# arduino-configuration-shield.net
KiCad netlist of a schematic drawn in EAGLE
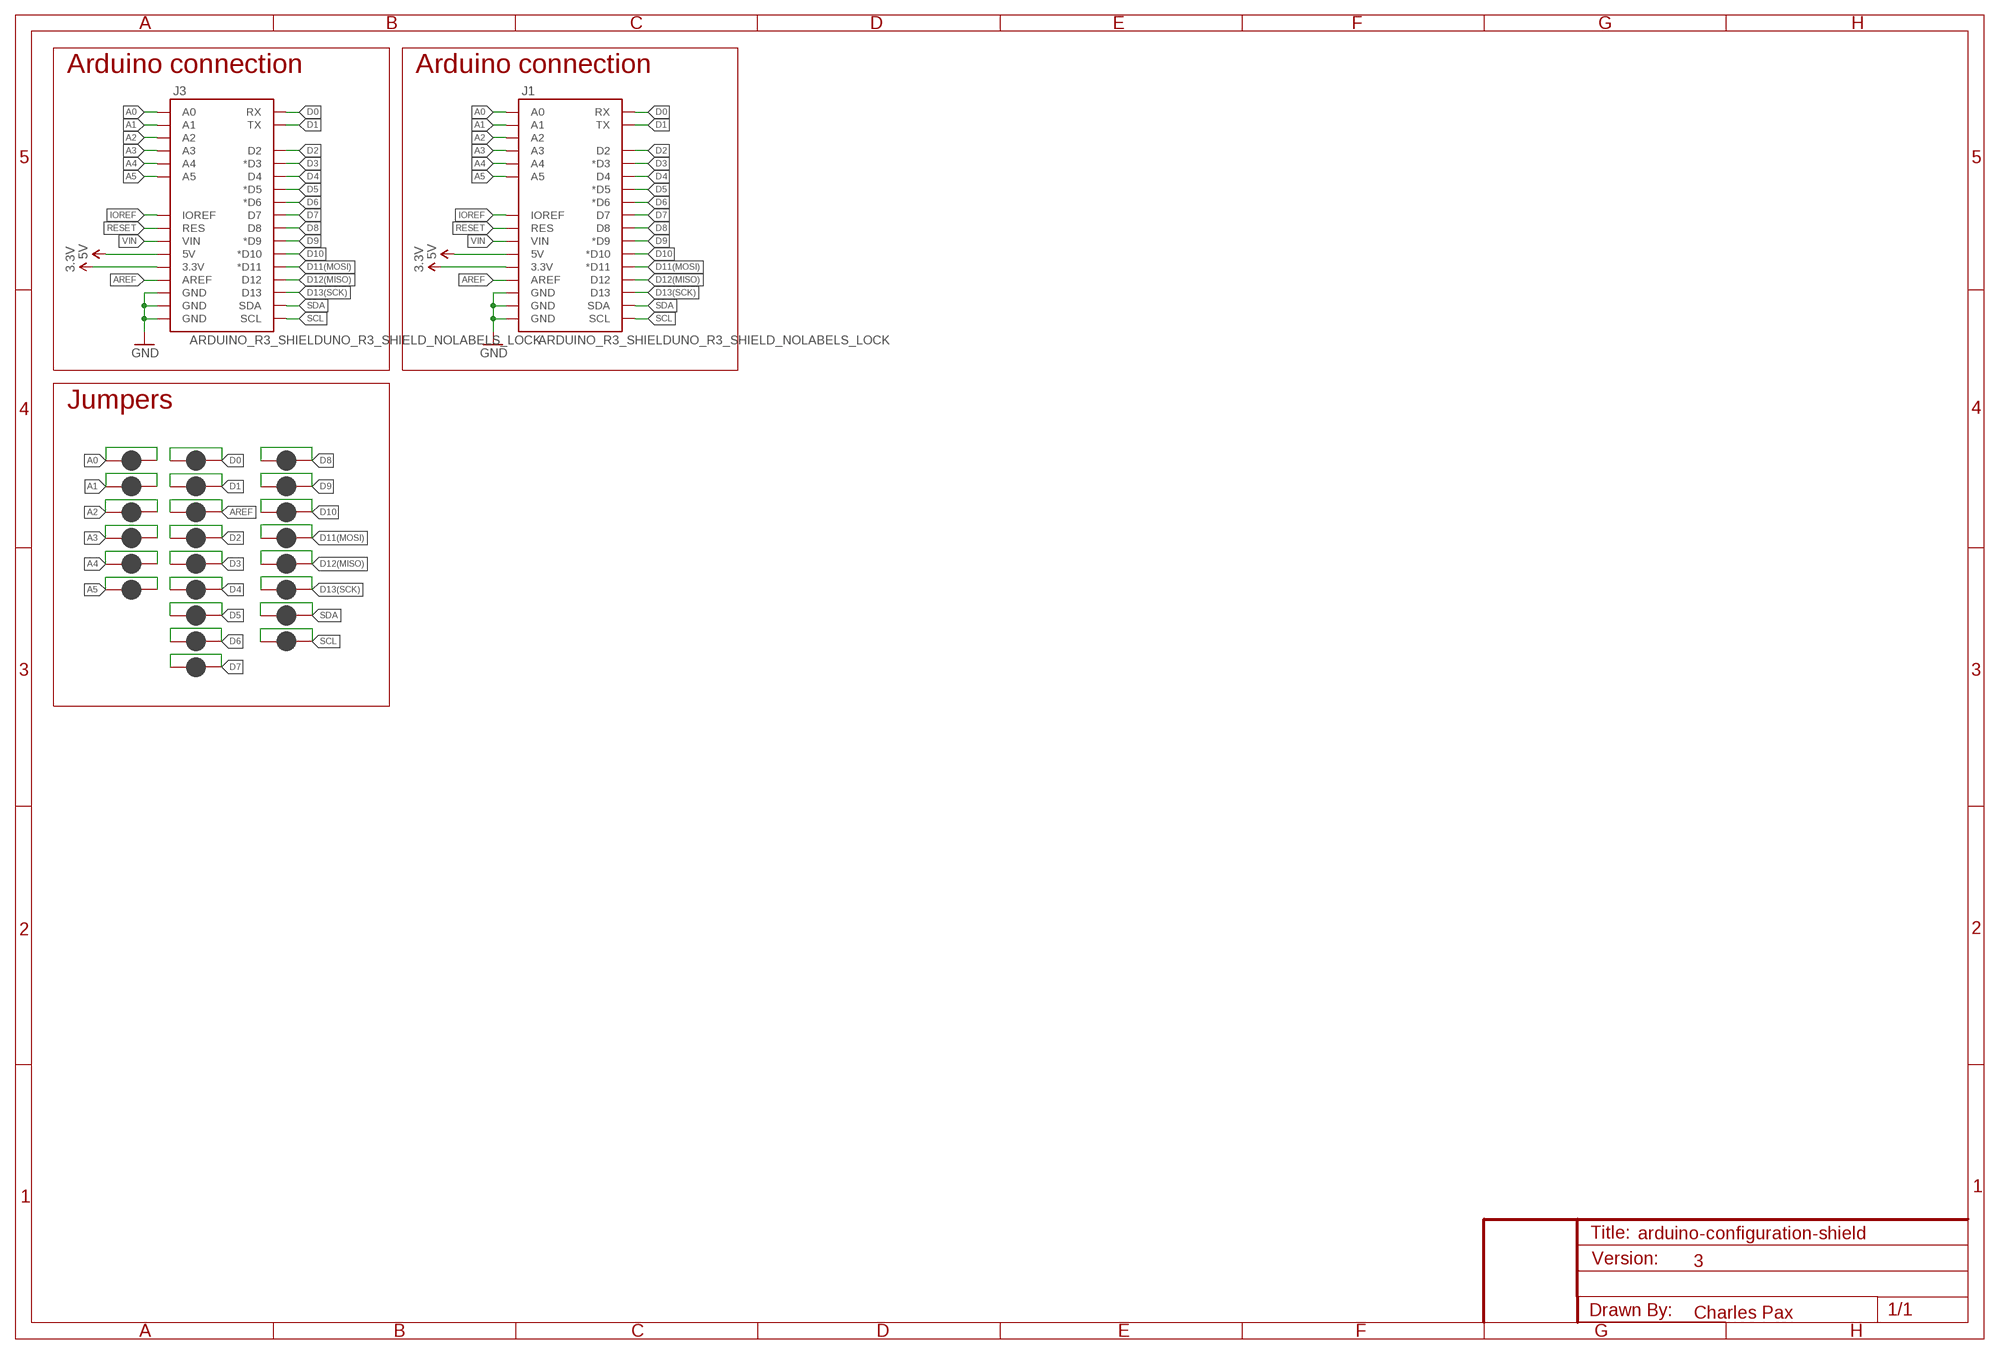
[diagram p0: schematic, sheet 1]

(export (version "E")
  (design (tool "Eeschema 10.0.6"))
  (components
    (comp (ref "J1")
      (value "ARDUINO_R3_SHIELDUNO_R3_SHIELD_NOLABELS_LOCK")
      (footprint "eagle-import:UNO_R3_SHIELD_NOLABELS_LOCK")
      (libsource (lib "eagle-import") (part "ARDUINO_R3_SHIELDUNO_R3_SHIELD_NOLABELS_LOCK"))
    )
    (comp (ref "J3")
      (value "ARDUINO_R3_SHIELDUNO_R3_SHIELD_NOLABELS_LOCK")
      (footprint "eagle-import:UNO_R3_SHIELD_NOLABELS_LOCK")
      (libsource (lib "eagle-import") (part "ARDUINO_R3_SHIELDUNO_R3_SHIELD_NOLABELS_LOCK"))
    )
    (comp (ref "SJ1")
      (value "JUMPER-PAD-2-NC_BY_PASTE")
      (footprint "eagle-import:PAD-JUMPER-2-NC_BY_PASTE_YES_SILK")
      (libsource (lib "eagle-import") (part "JUMPER-PAD-2-NC_BY_PASTE"))
    )
    (comp (ref "SJ2")
      (value "JUMPER-PAD-2-NC_BY_PASTE")
      (footprint "eagle-import:PAD-JUMPER-2-NC_BY_PASTE_YES_SILK")
      (libsource (lib "eagle-import") (part "JUMPER-PAD-2-NC_BY_PASTE"))
    )
    (comp (ref "SJ3")
      (value "JUMPER-PAD-2-NC_BY_PASTE")
      (footprint "eagle-import:PAD-JUMPER-2-NC_BY_PASTE_YES_SILK")
      (libsource (lib "eagle-import") (part "JUMPER-PAD-2-NC_BY_PASTE"))
    )
    (comp (ref "SJ4")
      (value "JUMPER-PAD-2-NC_BY_PASTE")
      (footprint "eagle-import:PAD-JUMPER-2-NC_BY_PASTE_YES_SILK")
      (libsource (lib "eagle-import") (part "JUMPER-PAD-2-NC_BY_PASTE"))
    )
    (comp (ref "SJ5")
      (value "JUMPER-PAD-2-NC_BY_PASTE")
      (footprint "eagle-import:PAD-JUMPER-2-NC_BY_PASTE_YES_SILK")
      (libsource (lib "eagle-import") (part "JUMPER-PAD-2-NC_BY_PASTE"))
    )
    (comp (ref "SJ6")
      (value "JUMPER-PAD-2-NC_BY_PASTE")
      (footprint "eagle-import:PAD-JUMPER-2-NC_BY_PASTE_YES_SILK")
      (libsource (lib "eagle-import") (part "JUMPER-PAD-2-NC_BY_PASTE"))
    )
    (comp (ref "SJ7")
      (value "JUMPER-PAD-2-NC_BY_PASTE")
      (footprint "eagle-import:PAD-JUMPER-2-NC_BY_PASTE_YES_SILK")
      (libsource (lib "eagle-import") (part "JUMPER-PAD-2-NC_BY_PASTE"))
    )
    (comp (ref "SJ8")
      (value "JUMPER-PAD-2-NC_BY_PASTE")
      (footprint "eagle-import:PAD-JUMPER-2-NC_BY_PASTE_YES_SILK")
      (libsource (lib "eagle-import") (part "JUMPER-PAD-2-NC_BY_PASTE"))
    )
    (comp (ref "SJ9")
      (value "JUMPER-PAD-2-NC_BY_PASTE")
      (footprint "eagle-import:PAD-JUMPER-2-NC_BY_PASTE_YES_SILK")
      (libsource (lib "eagle-import") (part "JUMPER-PAD-2-NC_BY_PASTE"))
    )
    (comp (ref "SJ10")
      (value "JUMPER-PAD-2-NC_BY_PASTE")
      (footprint "eagle-import:PAD-JUMPER-2-NC_BY_PASTE_YES_SILK")
      (libsource (lib "eagle-import") (part "JUMPER-PAD-2-NC_BY_PASTE"))
    )
    (comp (ref "SJ11")
      (value "JUMPER-PAD-2-NC_BY_PASTE")
      (footprint "eagle-import:PAD-JUMPER-2-NC_BY_PASTE_YES_SILK")
      (libsource (lib "eagle-import") (part "JUMPER-PAD-2-NC_BY_PASTE"))
    )
    (comp (ref "SJ12")
      (value "JUMPER-PAD-2-NC_BY_PASTE")
      (footprint "eagle-import:PAD-JUMPER-2-NC_BY_PASTE_YES_SILK")
      (libsource (lib "eagle-import") (part "JUMPER-PAD-2-NC_BY_PASTE"))
    )
    (comp (ref "SJ13")
      (value "JUMPER-PAD-2-NC_BY_PASTE")
      (footprint "eagle-import:PAD-JUMPER-2-NC_BY_PASTE_YES_SILK")
      (libsource (lib "eagle-import") (part "JUMPER-PAD-2-NC_BY_PASTE"))
    )
    (comp (ref "SJ14")
      (value "JUMPER-PAD-2-NC_BY_PASTE")
      (footprint "eagle-import:PAD-JUMPER-2-NC_BY_PASTE_YES_SILK")
      (libsource (lib "eagle-import") (part "JUMPER-PAD-2-NC_BY_PASTE"))
    )
    (comp (ref "SJ15")
      (value "JUMPER-PAD-2-NC_BY_PASTE")
      (footprint "eagle-import:PAD-JUMPER-2-NC_BY_PASTE_YES_SILK")
      (libsource (lib "eagle-import") (part "JUMPER-PAD-2-NC_BY_PASTE"))
    )
    (comp (ref "SJ19")
      (value "JUMPER-PAD-2-NC_BY_PASTE")
      (footprint "eagle-import:PAD-JUMPER-2-NC_BY_PASTE_YES_SILK")
      (libsource (lib "eagle-import") (part "JUMPER-PAD-2-NC_BY_PASTE"))
    )
    (comp (ref "SJ20")
      (value "JUMPER-PAD-2-NC_BY_PASTE")
      (footprint "eagle-import:PAD-JUMPER-2-NC_BY_PASTE_YES_SILK")
      (libsource (lib "eagle-import") (part "JUMPER-PAD-2-NC_BY_PASTE"))
    )
    (comp (ref "SJ21")
      (value "JUMPER-PAD-2-NC_BY_PASTE")
      (footprint "eagle-import:PAD-JUMPER-2-NC_BY_PASTE_YES_SILK")
      (libsource (lib "eagle-import") (part "JUMPER-PAD-2-NC_BY_PASTE"))
    )
    (comp (ref "SJ22")
      (value "JUMPER-PAD-2-NC_BY_PASTE")
      (footprint "eagle-import:PAD-JUMPER-2-NC_BY_PASTE_YES_SILK")
      (libsource (lib "eagle-import") (part "JUMPER-PAD-2-NC_BY_PASTE"))
    )
    (comp (ref "SJ23")
      (value "JUMPER-PAD-2-NC_BY_PASTE")
      (footprint "eagle-import:PAD-JUMPER-2-NC_BY_PASTE_YES_SILK")
      (libsource (lib "eagle-import") (part "JUMPER-PAD-2-NC_BY_PASTE"))
    )
    (comp (ref "SJ24")
      (value "JUMPER-PAD-2-NC_BY_PASTE")
      (footprint "eagle-import:PAD-JUMPER-2-NC_BY_PASTE_YES_SILK")
      (libsource (lib "eagle-import") (part "JUMPER-PAD-2-NC_BY_PASTE"))
    )
    (comp (ref "SJ25")
      (value "JUMPER-PAD-2-NC_BY_PASTE")
      (footprint "eagle-import:PAD-JUMPER-2-NC_BY_PASTE_YES_SILK")
      (libsource (lib "eagle-import") (part "JUMPER-PAD-2-NC_BY_PASTE"))
    )
    (comp (ref "SJ26")
      (value "JUMPER-PAD-2-NC_BY_PASTE")
      (footprint "eagle-import:PAD-JUMPER-2-NC_BY_PASTE_YES_SILK")
      (libsource (lib "eagle-import") (part "JUMPER-PAD-2-NC_BY_PASTE"))
    )
  )
  (nets
    (net (code "1") (name "3.3V") (class "Default")
      (node (ref "J1") (pin "3.3V") (pinfunction "3.3V_3.3V") (pintype "bidirectional"))
      (node (ref "J3") (pin "3.3V") (pinfunction "3.3V_3.3V") (pintype "bidirectional"))
    )
    (net (code "2") (name "5V") (class "Default")
      (node (ref "J1") (pin "5V") (pinfunction "5V_5V") (pintype "bidirectional"))
      (node (ref "J3") (pin "5V") (pinfunction "5V_5V") (pintype "bidirectional"))
    )
    (net (code "3") (name "A0") (class "Default")
      (node (ref "J1") (pin "A0") (pinfunction "A0_A0") (pintype "bidirectional"))
      (node (ref "J3") (pin "A0") (pinfunction "A0_A0") (pintype "bidirectional"))
      (node (ref "SJ10") (pin "1") (pinfunction "1_1") (pintype "passive"))
      (node (ref "SJ10") (pin "2") (pinfunction "2_2") (pintype "passive"))
    )
    (net (code "4") (name "A1") (class "Default")
      (node (ref "J1") (pin "A1") (pinfunction "A1_A1") (pintype "bidirectional"))
      (node (ref "J3") (pin "A1") (pinfunction "A1_A1") (pintype "bidirectional"))
      (node (ref "SJ7") (pin "1") (pinfunction "1_1") (pintype "passive"))
      (node (ref "SJ7") (pin "2") (pinfunction "2_2") (pintype "passive"))
    )
    (net (code "5") (name "A2") (class "Default")
      (node (ref "J1") (pin "A2") (pinfunction "A2_A2") (pintype "bidirectional"))
      (node (ref "J3") (pin "A2") (pinfunction "A2_A2") (pintype "bidirectional"))
      (node (ref "SJ11") (pin "1") (pinfunction "1_1") (pintype "passive"))
      (node (ref "SJ11") (pin "2") (pinfunction "2_2") (pintype "passive"))
    )
    (net (code "6") (name "A3") (class "Default")
      (node (ref "J1") (pin "A3") (pinfunction "A3_A3") (pintype "bidirectional"))
      (node (ref "J3") (pin "A3") (pinfunction "A3_A3") (pintype "bidirectional"))
      (node (ref "SJ12") (pin "1") (pinfunction "1_1") (pintype "passive"))
      (node (ref "SJ12") (pin "2") (pinfunction "2_2") (pintype "passive"))
    )
    (net (code "7") (name "A4") (class "Default")
      (node (ref "J1") (pin "A4") (pinfunction "A4_A4") (pintype "bidirectional"))
      (node (ref "J3") (pin "A4") (pinfunction "A4_A4") (pintype "bidirectional"))
      (node (ref "SJ13") (pin "1") (pinfunction "1_1") (pintype "passive"))
      (node (ref "SJ13") (pin "2") (pinfunction "2_2") (pintype "passive"))
    )
    (net (code "8") (name "A5") (class "Default")
      (node (ref "J1") (pin "A5") (pinfunction "A5_A5") (pintype "bidirectional"))
      (node (ref "J3") (pin "A5") (pinfunction "A5_A5") (pintype "bidirectional"))
      (node (ref "SJ14") (pin "1") (pinfunction "1_1") (pintype "passive"))
      (node (ref "SJ14") (pin "2") (pinfunction "2_2") (pintype "passive"))
    )
    (net (code "9") (name "AREF") (class "Default")
      (node (ref "J1") (pin "AREF") (pinfunction "AREF_AREF") (pintype "bidirectional"))
      (node (ref "J3") (pin "AREF") (pinfunction "AREF_AREF") (pintype "bidirectional"))
      (node (ref "SJ15") (pin "1") (pinfunction "1_1") (pintype "passive"))
      (node (ref "SJ15") (pin "2") (pinfunction "2_2") (pintype "passive"))
    )
    (net (code "10") (name "D0") (class "Default")
      (node (ref "J1") (pin "RX") (pinfunction "RX_RX") (pintype "bidirectional"))
      (node (ref "J3") (pin "RX") (pinfunction "RX_RX") (pintype "bidirectional"))
      (node (ref "SJ8") (pin "1") (pinfunction "1_1") (pintype "passive"))
      (node (ref "SJ8") (pin "2") (pinfunction "2_2") (pintype "passive"))
    )
    (net (code "11") (name "D1") (class "Default")
      (node (ref "J1") (pin "TX") (pinfunction "TX_TX") (pintype "bidirectional"))
      (node (ref "J3") (pin "TX") (pinfunction "TX_TX") (pintype "bidirectional"))
      (node (ref "SJ9") (pin "1") (pinfunction "1_1") (pintype "passive"))
      (node (ref "SJ9") (pin "2") (pinfunction "2_2") (pintype "passive"))
    )
    (net (code "12") (name "D2") (class "Default")
      (node (ref "J1") (pin "D2") (pinfunction "D2_D2") (pintype "bidirectional"))
      (node (ref "J3") (pin "D2") (pinfunction "D2_D2") (pintype "bidirectional"))
      (node (ref "SJ3") (pin "1") (pinfunction "1_1") (pintype "passive"))
      (node (ref "SJ3") (pin "2") (pinfunction "2_2") (pintype "passive"))
    )
    (net (code "13") (name "D3") (class "Default")
      (node (ref "J1") (pin "D3") (pinfunction "*D3_D3") (pintype "bidirectional"))
      (node (ref "J3") (pin "D3") (pinfunction "*D3_D3") (pintype "bidirectional"))
      (node (ref "SJ4") (pin "1") (pinfunction "1_1") (pintype "passive"))
      (node (ref "SJ4") (pin "2") (pinfunction "2_2") (pintype "passive"))
    )
    (net (code "14") (name "D4") (class "Default")
      (node (ref "J1") (pin "D4") (pinfunction "D4_D4") (pintype "bidirectional"))
      (node (ref "J3") (pin "D4") (pinfunction "D4_D4") (pintype "bidirectional"))
      (node (ref "SJ5") (pin "1") (pinfunction "1_1") (pintype "passive"))
      (node (ref "SJ5") (pin "2") (pinfunction "2_2") (pintype "passive"))
    )
    (net (code "15") (name "D5") (class "Default")
      (node (ref "J1") (pin "D5") (pinfunction "*D5_D5") (pintype "bidirectional"))
      (node (ref "J3") (pin "D5") (pinfunction "*D5_D5") (pintype "bidirectional"))
      (node (ref "SJ6") (pin "1") (pinfunction "1_1") (pintype "passive"))
      (node (ref "SJ6") (pin "2") (pinfunction "2_2") (pintype "passive"))
    )
    (net (code "16") (name "D6") (class "Default")
      (node (ref "J1") (pin "D6") (pinfunction "*D6_D6") (pintype "bidirectional"))
      (node (ref "J3") (pin "D6") (pinfunction "*D6_D6") (pintype "bidirectional"))
      (node (ref "SJ19") (pin "1") (pinfunction "1_1") (pintype "passive"))
      (node (ref "SJ19") (pin "2") (pinfunction "2_2") (pintype "passive"))
    )
    (net (code "17") (name "D7") (class "Default")
      (node (ref "J1") (pin "D7") (pinfunction "D7_D7") (pintype "bidirectional"))
      (node (ref "J3") (pin "D7") (pinfunction "D7_D7") (pintype "bidirectional"))
      (node (ref "SJ20") (pin "1") (pinfunction "1_1") (pintype "passive"))
      (node (ref "SJ20") (pin "2") (pinfunction "2_2") (pintype "passive"))
    )
    (net (code "18") (name "D8") (class "Default")
      (node (ref "J1") (pin "D8") (pinfunction "D8_D8") (pintype "bidirectional"))
      (node (ref "J3") (pin "D8") (pinfunction "D8_D8") (pintype "bidirectional"))
      (node (ref "SJ21") (pin "1") (pinfunction "1_1") (pintype "passive"))
      (node (ref "SJ21") (pin "2") (pinfunction "2_2") (pintype "passive"))
    )
    (net (code "19") (name "D9") (class "Default")
      (node (ref "J1") (pin "D9") (pinfunction "*D9_D9") (pintype "bidirectional"))
      (node (ref "J3") (pin "D9") (pinfunction "*D9_D9") (pintype "bidirectional"))
      (node (ref "SJ22") (pin "1") (pinfunction "1_1") (pintype "passive"))
      (node (ref "SJ22") (pin "2") (pinfunction "2_2") (pintype "passive"))
    )
    (net (code "20") (name "D10") (class "Default")
      (node (ref "J1") (pin "D10") (pinfunction "*D10_D10") (pintype "bidirectional"))
      (node (ref "J3") (pin "D10") (pinfunction "*D10_D10") (pintype "bidirectional"))
      (node (ref "SJ23") (pin "1") (pinfunction "1_1") (pintype "passive"))
      (node (ref "SJ23") (pin "2") (pinfunction "2_2") (pintype "passive"))
    )
    (net (code "21") (name "D11(MOSI)") (class "Default")
      (node (ref "J1") (pin "D11") (pinfunction "*D11_D11") (pintype "bidirectional"))
      (node (ref "J3") (pin "D11") (pinfunction "*D11_D11") (pintype "bidirectional"))
      (node (ref "SJ24") (pin "1") (pinfunction "1_1") (pintype "passive"))
      (node (ref "SJ24") (pin "2") (pinfunction "2_2") (pintype "passive"))
    )
    (net (code "22") (name "D12(MISO)") (class "Default")
      (node (ref "J1") (pin "D12") (pinfunction "D12_D12") (pintype "bidirectional"))
      (node (ref "J3") (pin "D12") (pinfunction "D12_D12") (pintype "bidirectional"))
      (node (ref "SJ25") (pin "1") (pinfunction "1_1") (pintype "passive"))
      (node (ref "SJ25") (pin "2") (pinfunction "2_2") (pintype "passive"))
    )
    (net (code "23") (name "D13(SCK)") (class "Default")
      (node (ref "J1") (pin "D13") (pinfunction "D13_D13") (pintype "bidirectional"))
      (node (ref "J3") (pin "D13") (pinfunction "D13_D13") (pintype "bidirectional"))
      (node (ref "SJ26") (pin "1") (pinfunction "1_1") (pintype "passive"))
      (node (ref "SJ26") (pin "2") (pinfunction "2_2") (pintype "passive"))
    )
    (net (code "24") (name "GND") (class "Default")
      (node (ref "J1") (pin "GND@0") (pinfunction "GND_GND@0") (pintype "bidirectional"))
      (node (ref "J1") (pin "GND@1") (pinfunction "GND_GND@1") (pintype "bidirectional"))
      (node (ref "J1") (pin "GND@2") (pinfunction "GND_GND@2") (pintype "bidirectional"))
      (node (ref "J3") (pin "GND@0") (pinfunction "GND_GND@0") (pintype "bidirectional"))
      (node (ref "J3") (pin "GND@1") (pinfunction "GND_GND@1") (pintype "bidirectional"))
      (node (ref "J3") (pin "GND@2") (pinfunction "GND_GND@2") (pintype "bidirectional"))
    )
    (net (code "25") (name "IOREF") (class "Default")
      (node (ref "J1") (pin "IOREF") (pinfunction "IOREF_IOREF") (pintype "bidirectional"))
      (node (ref "J3") (pin "IOREF") (pinfunction "IOREF_IOREF") (pintype "bidirectional"))
    )
    (net (code "26") (name "RESET") (class "Default")
      (node (ref "J1") (pin "RES") (pinfunction "RES_RES") (pintype "bidirectional"))
      (node (ref "J3") (pin "RES") (pinfunction "RES_RES") (pintype "bidirectional"))
    )
    (net (code "27") (name "SCL") (class "Default")
      (node (ref "J1") (pin "SCL") (pinfunction "SCL_SCL") (pintype "bidirectional"))
      (node (ref "J3") (pin "SCL") (pinfunction "SCL_SCL") (pintype "bidirectional"))
      (node (ref "SJ2") (pin "1") (pinfunction "1_1") (pintype "passive"))
      (node (ref "SJ2") (pin "2") (pinfunction "2_2") (pintype "passive"))
    )
    (net (code "28") (name "SDA") (class "Default")
      (node (ref "J1") (pin "SDA") (pinfunction "SDA_SDA") (pintype "bidirectional"))
      (node (ref "J3") (pin "SDA") (pinfunction "SDA_SDA") (pintype "bidirectional"))
      (node (ref "SJ1") (pin "1") (pinfunction "1_1") (pintype "passive"))
      (node (ref "SJ1") (pin "2") (pinfunction "2_2") (pintype "passive"))
    )
    (net (code "29") (name "VIN") (class "Default")
      (node (ref "J1") (pin "VIN") (pinfunction "VIN_VIN") (pintype "bidirectional"))
      (node (ref "J3") (pin "VIN") (pinfunction "VIN_VIN") (pintype "bidirectional"))
    )
  )
)
